# 07-CAN_UART.net
KiCad netlist of a schematic drawn in Altium Designer
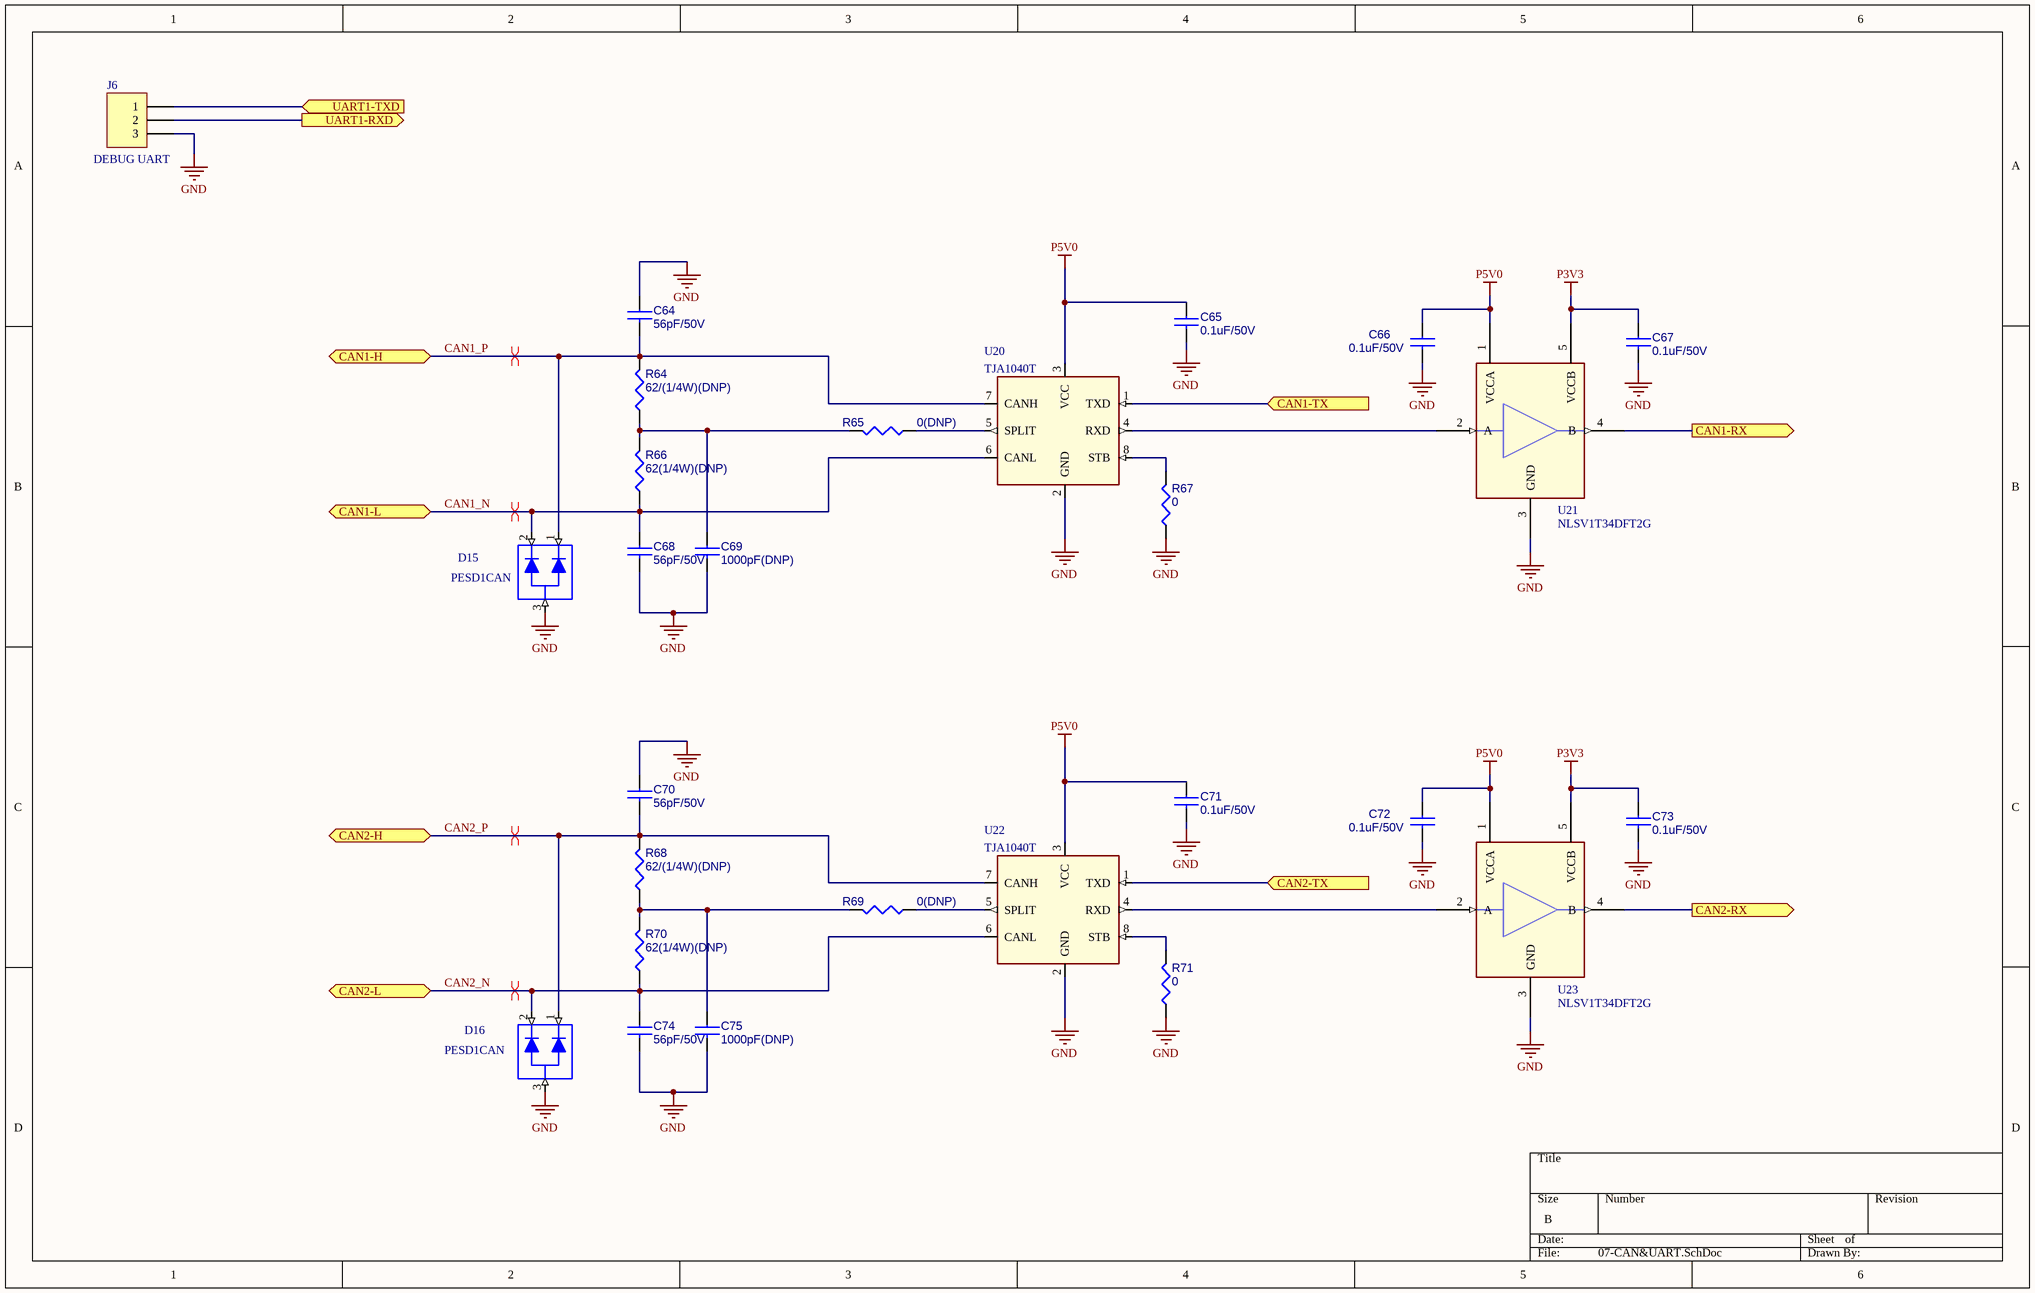
[diagram p0: 07-CAN&UART.SchDoc]

(export (version "E")
  (design (tool "Eeschema 10.0.6"))
  (components
    (comp (ref "C64") (value "56pF/50V") (libsource (lib "*") (part "P_CAP NP")))
    (comp (ref "C65") (value "0.1uF/50V") (libsource (lib "*") (part "P_CAP NP")))
    (comp (ref "C66") (value "0.1uF/50V") (libsource (lib "*") (part "P_CAP NP")))
    (comp (ref "C67") (value "0.1uF/50V") (libsource (lib "*") (part "P_CAP NP")))
    (comp (ref "C68") (value "56pF/50V") (libsource (lib "*") (part "P_CAP NP")))
    (comp (ref "C69") (value "1000pF(DNP)") (libsource (lib "*") (part "P_CAP NP")))
    (comp (ref "C70") (value "56pF/50V") (libsource (lib "*") (part "P_CAP NP")))
    (comp (ref "C71") (value "0.1uF/50V") (libsource (lib "*") (part "P_CAP NP")))
    (comp (ref "C72") (value "0.1uF/50V") (libsource (lib "*") (part "P_CAP NP")))
    (comp (ref "C73") (value "0.1uF/50V") (libsource (lib "*") (part "P_CAP NP")))
    (comp (ref "C74") (value "56pF/50V") (libsource (lib "*") (part "P_CAP NP")))
    (comp (ref "C75") (value "1000pF(DNP)") (libsource (lib "*") (part "P_CAP NP")))
    (comp (ref "D15")
      (value "PESD1CAN")
      (footprint "PESD2CAN")
      (fields (field (name "PART NUMBER") "SCA00000J00"))
      (libsource (lib "Schlib") (part "PESD2CAN"))
    )
    (comp (ref "D16")
      (value "PESD1CAN")
      (footprint "PESD2CAN")
      (fields (field (name "PART NUMBER") "SCA00000J00"))
      (libsource (lib "Schlib") (part "PESD2CAN"))
    )
    (comp (ref "J6")
      (value "DEBUG UART")
      (footprint "HDR1X3")
      (description "Header, 3-Pin")
      (fields (field (name "PUBLISHER") "Altium Limited"))
      (libsource (lib "Miscellaneous Connectors") (part "Header 3"))
    )
    (comp (ref "R64") (value "62/(1/4W)(DNP)") (footprint "1206") (libsource (lib "*") (part "P_R")))
    (comp (ref "R65") (value "0(DNP)") (footprint "0402") (libsource (lib "*") (part "P_R")))
    (comp (ref "R66") (value "62(1/4W)(DNP)") (footprint "1206") (libsource (lib "*") (part "P_R")))
    (comp (ref "R67") (value "0") (footprint "0402") (libsource (lib "*") (part "P_R")))
    (comp (ref "R68") (value "62/(1/4W)(DNP)") (footprint "1206") (libsource (lib "*") (part "P_R")))
    (comp (ref "R69") (value "0(DNP)") (footprint "0402") (libsource (lib "*") (part "P_R")))
    (comp (ref "R70") (value "62(1/4W)(DNP)") (footprint "1206") (libsource (lib "*") (part "P_R")))
    (comp (ref "R71") (value "0") (footprint "0402") (libsource (lib "*") (part "P_R")))
    (comp (ref "U20")
      (value "TJA1040T")
      (footprint "SO8")
      (description "IC XCVR CAN HS 5V SO8")
      (libsource (lib "*") (part "TJA1040T_SO_8P"))
    )
    (comp (ref "U21")
      (value "NLSV1T34DFT2G")
      (footprint "SC70")
      (libsource (lib "Schlib") (part "NLSV1T34DFT2G"))
    )
    (comp (ref "U22")
      (value "TJA1040T")
      (footprint "SO8")
      (description "IC XCVR CAN HS 5V SO8")
      (libsource (lib "*") (part "TJA1040T_SO_8P"))
    )
    (comp (ref "U23")
      (value "NLSV1T34DFT2G")
      (footprint "SC70")
      (libsource (lib "Schlib") (part "NLSV1T34DFT2G"))
    )
  )
  (nets
    (net (code "1") (name "/CAN1-RX") (class "Default")
      (node (ref "U21") (pin "4") (pinfunction "B_4") (pintype "output"))
    )
    (net (code "2") (name "/CAN1-TX") (class "Default")
      (node (ref "U20") (pin "1") (pinfunction "TXD_1") (pintype "input"))
    )
    (net (code "3") (name "/CAN1_N") (class "Default")
      (node (ref "C68") (pin "1") (pinfunction "1_1") (pintype "passive"))
      (node (ref "D15") (pin "2") (pinfunction "2_2") (pintype "input"))
      (node (ref "R66") (pin "2") (pinfunction "2_2") (pintype "passive"))
      (node (ref "U20") (pin "6") (pinfunction "CANL_6") (pintype "bidirectional"))
    )
    (net (code "4") (name "/CAN1_P") (class "Default")
      (node (ref "C64") (pin "2") (pinfunction "2_2") (pintype "passive"))
      (node (ref "D15") (pin "1") (pinfunction "1_1") (pintype "input"))
      (node (ref "R64") (pin "1") (pinfunction "1_1") (pintype "passive"))
      (node (ref "U20") (pin "7") (pinfunction "CANH_7") (pintype "bidirectional"))
    )
    (net (code "5") (name "/CAN2-RX") (class "Default")
      (node (ref "U23") (pin "4") (pinfunction "B_4") (pintype "output"))
    )
    (net (code "6") (name "/CAN2-TX") (class "Default")
      (node (ref "U22") (pin "1") (pinfunction "TXD_1") (pintype "input"))
    )
    (net (code "7") (name "/CAN2_N") (class "Default")
      (node (ref "C74") (pin "1") (pinfunction "1_1") (pintype "passive"))
      (node (ref "D16") (pin "2") (pinfunction "2_2") (pintype "input"))
      (node (ref "R70") (pin "2") (pinfunction "2_2") (pintype "passive"))
      (node (ref "U22") (pin "6") (pinfunction "CANL_6") (pintype "bidirectional"))
    )
    (net (code "8") (name "/CAN2_P") (class "Default")
      (node (ref "C70") (pin "2") (pinfunction "2_2") (pintype "passive"))
      (node (ref "D16") (pin "1") (pinfunction "1_1") (pintype "input"))
      (node (ref "R68") (pin "1") (pinfunction "1_1") (pintype "passive"))
      (node (ref "U22") (pin "7") (pinfunction "CANH_7") (pintype "bidirectional"))
    )
    (net (code "9") (name "/UART1-RXD") (class "Default")
      (node (ref "J6") (pin "2") (pinfunction "2_2") (pintype "passive"))
    )
    (net (code "10") (name "/UART1-TXD") (class "Default")
      (node (ref "J6") (pin "1") (pinfunction "1_1") (pintype "passive"))
    )
    (net (code "11") (name "GND") (class "Default")
      (node (ref "C64") (pin "1") (pinfunction "1_1") (pintype "passive"))
      (node (ref "C65") (pin "2") (pinfunction "2_2") (pintype "passive"))
      (node (ref "C66") (pin "2") (pinfunction "2_2") (pintype "passive"))
      (node (ref "C67") (pin "2") (pinfunction "2_2") (pintype "passive"))
      (node (ref "C68") (pin "2") (pinfunction "2_2") (pintype "passive"))
      (node (ref "C69") (pin "2") (pinfunction "2_2") (pintype "passive"))
      (node (ref "C70") (pin "1") (pinfunction "1_1") (pintype "passive"))
      (node (ref "C71") (pin "2") (pinfunction "2_2") (pintype "passive"))
      (node (ref "C72") (pin "2") (pinfunction "2_2") (pintype "passive"))
      (node (ref "C73") (pin "2") (pinfunction "2_2") (pintype "passive"))
      (node (ref "C74") (pin "2") (pinfunction "2_2") (pintype "passive"))
      (node (ref "C75") (pin "2") (pinfunction "2_2") (pintype "passive"))
      (node (ref "D15") (pin "3") (pinfunction "3_3") (pintype "input"))
      (node (ref "D16") (pin "3") (pinfunction "3_3") (pintype "input"))
      (node (ref "J6") (pin "3") (pinfunction "3_3") (pintype "passive"))
      (node (ref "R67") (pin "2") (pinfunction "2_2") (pintype "passive"))
      (node (ref "R71") (pin "2") (pinfunction "2_2") (pintype "passive"))
      (node (ref "U20") (pin "2") (pinfunction "GND_2") (pintype "power_in"))
      (node (ref "U21") (pin "3") (pinfunction "GND_3") (pintype "power_in"))
      (node (ref "U22") (pin "2") (pinfunction "GND_2") (pintype "power_in"))
      (node (ref "U23") (pin "3") (pinfunction "GND_3") (pintype "power_in"))
    )
    (net (code "12") (name "Net-(C69-Pad1)") (class "Default")
      (node (ref "C69") (pin "1") (pinfunction "1_1") (pintype "passive"))
      (node (ref "R64") (pin "2") (pinfunction "2_2") (pintype "passive"))
      (node (ref "R65") (pin "1") (pinfunction "1_1") (pintype "passive"))
      (node (ref "R66") (pin "1") (pinfunction "1_1") (pintype "passive"))
    )
    (net (code "13") (name "Net-(C75-Pad1)") (class "Default")
      (node (ref "C75") (pin "1") (pinfunction "1_1") (pintype "passive"))
      (node (ref "R68") (pin "2") (pinfunction "2_2") (pintype "passive"))
      (node (ref "R69") (pin "1") (pinfunction "1_1") (pintype "passive"))
      (node (ref "R70") (pin "1") (pinfunction "1_1") (pintype "passive"))
    )
    (net (code "14") (name "Net-(U20-RXD)") (class "Default")
      (node (ref "U20") (pin "4") (pinfunction "RXD_4") (pintype "output"))
      (node (ref "U21") (pin "2") (pinfunction "A_2") (pintype "input"))
    )
    (net (code "15") (name "Net-(U20-SPLIT)") (class "Default")
      (node (ref "R65") (pin "2") (pinfunction "2_2") (pintype "passive"))
      (node (ref "U20") (pin "5") (pinfunction "SPLIT_5") (pintype "output"))
    )
    (net (code "16") (name "Net-(U20-STB)") (class "Default")
      (node (ref "R67") (pin "1") (pinfunction "1_1") (pintype "passive"))
      (node (ref "U20") (pin "8") (pinfunction "STB_8") (pintype "input"))
    )
    (net (code "17") (name "Net-(U22-RXD)") (class "Default")
      (node (ref "U22") (pin "4") (pinfunction "RXD_4") (pintype "output"))
      (node (ref "U23") (pin "2") (pinfunction "A_2") (pintype "input"))
    )
    (net (code "18") (name "Net-(U22-SPLIT)") (class "Default")
      (node (ref "R69") (pin "2") (pinfunction "2_2") (pintype "passive"))
      (node (ref "U22") (pin "5") (pinfunction "SPLIT_5") (pintype "output"))
    )
    (net (code "19") (name "Net-(U22-STB)") (class "Default")
      (node (ref "R71") (pin "1") (pinfunction "1_1") (pintype "passive"))
      (node (ref "U22") (pin "8") (pinfunction "STB_8") (pintype "input"))
    )
    (net (code "20") (name "P3V3") (class "Default")
      (node (ref "C67") (pin "1") (pinfunction "1_1") (pintype "passive"))
      (node (ref "C73") (pin "1") (pinfunction "1_1") (pintype "passive"))
      (node (ref "U21") (pin "5") (pinfunction "VCCB_5") (pintype "power_in"))
      (node (ref "U23") (pin "5") (pinfunction "VCCB_5") (pintype "power_in"))
    )
    (net (code "21") (name "P5V0") (class "Default")
      (node (ref "C65") (pin "1") (pinfunction "1_1") (pintype "passive"))
      (node (ref "C66") (pin "1") (pinfunction "1_1") (pintype "passive"))
      (node (ref "C71") (pin "1") (pinfunction "1_1") (pintype "passive"))
      (node (ref "C72") (pin "1") (pinfunction "1_1") (pintype "passive"))
      (node (ref "U20") (pin "3") (pinfunction "VCC_3") (pintype "power_in"))
      (node (ref "U21") (pin "1") (pinfunction "VCCA_1") (pintype "power_in"))
      (node (ref "U22") (pin "3") (pinfunction "VCC_3") (pintype "power_in"))
      (node (ref "U23") (pin "1") (pinfunction "VCCA_1") (pintype "power_in"))
    )
  )
)
